# schematic.net
KiCad netlist of a schematic drawn in EAGLE
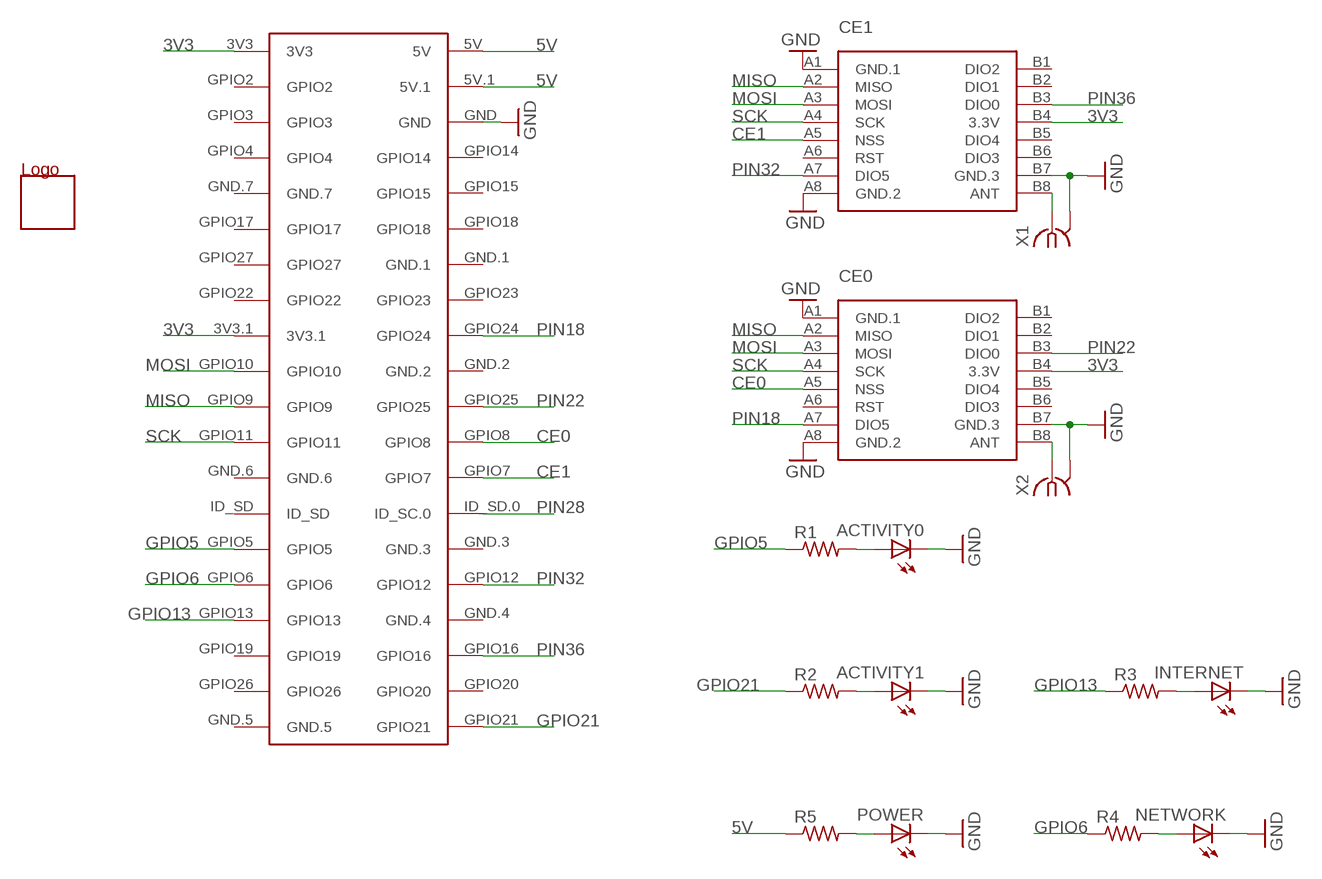
[diagram p0: schematic, sheet 1]

(export (version "E")
  (design (tool "Eeschema 10.0.6"))
  (components
    (comp (ref "ACTIVITY0")
      (value "LEDCHIPLED_0805")
      (footprint "eagle-import:CHIPLED_0805")
      (libsource (lib "eagle-import") (part "LEDCHIPLED_0805"))
    )
    (comp (ref "ACTIVITY1")
      (value "LEDCHIPLED_0805")
      (footprint "eagle-import:CHIPLED_0805")
      (libsource (lib "eagle-import") (part "LEDCHIPLED_0805"))
    )
    (comp (ref "CE0")
      (value "WIRELESS-LORA-RFM95W#SMD")
      (footprint "eagle-import:WIRELESS-LORA-RFM95W#SMD")
      (libsource (lib "eagle-import") (part "WIRELESS-LORA-RFM95W#SMD"))
    )
    (comp (ref "CE1")
      (value "WIRELESS-LORA-RFM95W#SMD")
      (footprint "eagle-import:WIRELESS-LORA-RFM95W#SMD")
      (libsource (lib "eagle-import") (part "WIRELESS-LORA-RFM95W#SMD"))
    )
    (comp (ref "INTERNET")
      (value "LEDCHIPLED_0805")
      (footprint "eagle-import:CHIPLED_0805")
      (libsource (lib "eagle-import") (part "LEDCHIPLED_0805"))
    )
    (comp (ref "NETWORK")
      (value "LEDCHIPLED_0805")
      (footprint "eagle-import:CHIPLED_0805")
      (libsource (lib "eagle-import") (part "LEDCHIPLED_0805"))
    )
    (comp (ref "POWER")
      (value "LEDCHIPLED_0805")
      (footprint "eagle-import:CHIPLED_0805")
      (libsource (lib "eagle-import") (part "LEDCHIPLED_0805"))
    )
    (comp (ref "R1")
      (value "R-US_R0805")
      (footprint "eagle-import:R0805")
      (libsource (lib "eagle-import") (part "R-US_R0805"))
    )
    (comp (ref "R2")
      (value "R-US_R0805")
      (footprint "eagle-import:R0805")
      (libsource (lib "eagle-import") (part "R-US_R0805"))
    )
    (comp (ref "R3")
      (value "R-US_R0805")
      (footprint "eagle-import:R0805")
      (libsource (lib "eagle-import") (part "R-US_R0805"))
    )
    (comp (ref "R4")
      (value "R-US_R0805")
      (footprint "eagle-import:R0805")
      (libsource (lib "eagle-import") (part "R-US_R0805"))
    )
    (comp (ref "R5")
      (value "R-US_R0805")
      (footprint "eagle-import:R0805")
      (libsource (lib "eagle-import") (part "R-US_R0805"))
    )
    (comp (ref "U$1")
      (value "PIZERO")
      (footprint "eagle-import:PIZERO")
      (libsource (lib "eagle-import") (part "PIZERO"))
    )
    (comp (ref "U$2")
      (value "REGANLOGO")
      (footprint "eagle-import:REGANLOGO")
      (libsource (lib "eagle-import") (part "REGANLOGO"))
    )
    (comp (ref "X1")
      (value "BU-SMA-V")
      (footprint "eagle-import:BU-SMA-V")
      (libsource (lib "eagle-import") (part "BU-SMA-V"))
    )
    (comp (ref "X2")
      (value "BU-SMA-V")
      (footprint "eagle-import:BU-SMA-V")
      (libsource (lib "eagle-import") (part "BU-SMA-V"))
    )
  )
  (nets
    (net (code "1") (name "/3V3") (class "Default")
      (node (ref "CE0") (pin "B4") (pinfunction "3.3V_B4") (pintype "power_in"))
      (node (ref "CE1") (pin "B4") (pinfunction "3.3V_B4") (pintype "power_in"))
      (node (ref "U$1") (pin "3V3") (pinfunction "3V3_3V3") (pintype "bidirectional"))
      (node (ref "U$1") (pin "3V3.1") (pinfunction "3V3.1_3V3.1") (pintype "bidirectional"))
    )
    (net (code "2") (name "/5V") (class "Default")
      (node (ref "R5") (pin "1") (pinfunction "1_1") (pintype "passive"))
      (node (ref "U$1") (pin "5V") (pinfunction "5V_5V") (pintype "bidirectional"))
      (node (ref "U$1") (pin "5V.1") (pinfunction "5V.1_5V.1") (pintype "bidirectional"))
    )
    (net (code "3") (name "/CE0") (class "Default")
      (node (ref "CE0") (pin "A5") (pinfunction "NSS_A5") (pintype "bidirectional"))
      (node (ref "U$1") (pin "GPIO8") (pinfunction "GPIO8_GPIO8") (pintype "bidirectional"))
    )
    (net (code "4") (name "/CE1") (class "Default")
      (node (ref "CE1") (pin "A5") (pinfunction "NSS_A5") (pintype "bidirectional"))
      (node (ref "U$1") (pin "GPIO7") (pinfunction "GPIO7_GPIO7") (pintype "bidirectional"))
    )
    (net (code "5") (name "/GPIO5") (class "Default")
      (node (ref "R1") (pin "1") (pinfunction "1_1") (pintype "passive"))
      (node (ref "U$1") (pin "GPIO5") (pinfunction "GPIO5_GPIO5") (pintype "bidirectional"))
    )
    (net (code "6") (name "/GPIO6") (class "Default")
      (node (ref "R4") (pin "1") (pinfunction "1_1") (pintype "passive"))
      (node (ref "U$1") (pin "GPIO6") (pinfunction "GPIO6_GPIO6") (pintype "bidirectional"))
    )
    (net (code "7") (name "/GPIO13") (class "Default")
      (node (ref "R3") (pin "1") (pinfunction "1_1") (pintype "passive"))
      (node (ref "U$1") (pin "GPIO13") (pinfunction "GPIO13_GPIO13") (pintype "bidirectional"))
    )
    (net (code "8") (name "/GPIO21") (class "Default")
      (node (ref "R2") (pin "1") (pinfunction "1_1") (pintype "passive"))
      (node (ref "U$1") (pin "GPIO21") (pinfunction "GPIO21_GPIO21") (pintype "bidirectional"))
    )
    (net (code "9") (name "/MISO") (class "Default")
      (node (ref "CE0") (pin "A2") (pinfunction "MISO_A2") (pintype "bidirectional"))
      (node (ref "CE1") (pin "A2") (pinfunction "MISO_A2") (pintype "bidirectional"))
      (node (ref "U$1") (pin "GPIO9") (pinfunction "GPIO9_GPIO9") (pintype "bidirectional"))
    )
    (net (code "10") (name "/MOSI") (class "Default")
      (node (ref "CE0") (pin "A3") (pinfunction "MOSI_A3") (pintype "bidirectional"))
      (node (ref "CE1") (pin "A3") (pinfunction "MOSI_A3") (pintype "bidirectional"))
      (node (ref "U$1") (pin "GPIO10") (pinfunction "GPIO10_GPIO10") (pintype "bidirectional"))
    )
    (net (code "11") (name "/PIN18") (class "Default")
      (node (ref "CE0") (pin "A7") (pinfunction "DIO5_A7") (pintype "bidirectional"))
      (node (ref "U$1") (pin "GPIO24") (pinfunction "GPIO24_GPIO24") (pintype "bidirectional"))
    )
    (net (code "12") (name "/PIN22") (class "Default")
      (node (ref "CE0") (pin "B3") (pinfunction "DIO0_B3") (pintype "bidirectional"))
      (node (ref "U$1") (pin "GPIO25") (pinfunction "GPIO25_GPIO25") (pintype "bidirectional"))
    )
    (net (code "13") (name "/PIN28") (class "Default")
      (node (ref "U$1") (pin "ID_SD.0") (pinfunction "ID_SC.0_ID_SD.0") (pintype "bidirectional"))
    )
    (net (code "14") (name "/PIN32") (class "Default")
      (node (ref "CE1") (pin "A7") (pinfunction "DIO5_A7") (pintype "bidirectional"))
      (node (ref "U$1") (pin "GPIO12") (pinfunction "GPIO12_GPIO12") (pintype "bidirectional"))
    )
    (net (code "15") (name "/PIN36") (class "Default")
      (node (ref "CE1") (pin "B3") (pinfunction "DIO0_B3") (pintype "bidirectional"))
      (node (ref "U$1") (pin "GPIO16") (pinfunction "GPIO16_GPIO16") (pintype "bidirectional"))
    )
    (net (code "16") (name "/SCK") (class "Default")
      (node (ref "CE0") (pin "A4") (pinfunction "SCK_A4") (pintype "bidirectional"))
      (node (ref "CE1") (pin "A4") (pinfunction "SCK_A4") (pintype "bidirectional"))
      (node (ref "U$1") (pin "GPIO11") (pinfunction "GPIO11_GPIO11") (pintype "bidirectional"))
    )
    (net (code "17") (name "GND") (class "Default")
      (node (ref "ACTIVITY0") (pin "C") (pinfunction "C_C") (pintype "passive"))
      (node (ref "ACTIVITY1") (pin "C") (pinfunction "C_C") (pintype "passive"))
      (node (ref "CE0") (pin "A1") (pinfunction "GND.1_A1") (pintype "power_in"))
      (node (ref "CE0") (pin "A8") (pinfunction "GND.2_A8") (pintype "power_in"))
      (node (ref "CE0") (pin "B7") (pinfunction "GND.3_B7") (pintype "power_in"))
      (node (ref "CE1") (pin "A1") (pinfunction "GND.1_A1") (pintype "power_in"))
      (node (ref "CE1") (pin "A8") (pinfunction "GND.2_A8") (pintype "power_in"))
      (node (ref "CE1") (pin "B7") (pinfunction "GND.3_B7") (pintype "power_in"))
      (node (ref "INTERNET") (pin "C") (pinfunction "C_C") (pintype "passive"))
      (node (ref "NETWORK") (pin "C") (pinfunction "C_C") (pintype "passive"))
      (node (ref "POWER") (pin "C") (pinfunction "C_C") (pintype "passive"))
      (node (ref "U$1") (pin "GND") (pinfunction "GND_GND") (pintype "bidirectional"))
      (node (ref "X1") (pin "2") (pinfunction "2_2") (pintype "passive"))
      (node (ref "X1") (pin "3") (pinfunction "2_3") (pintype "passive"))
      (node (ref "X1") (pin "4") (pinfunction "2_4") (pintype "passive"))
      (node (ref "X1") (pin "5") (pinfunction "2_5") (pintype "passive"))
      (node (ref "X2") (pin "2") (pinfunction "2_2") (pintype "passive"))
      (node (ref "X2") (pin "3") (pinfunction "2_3") (pintype "passive"))
      (node (ref "X2") (pin "4") (pinfunction "2_4") (pintype "passive"))
      (node (ref "X2") (pin "5") (pinfunction "2_5") (pintype "passive"))
    )
    (net (code "18") (name "Net-(ACTIVITY0-PadA)") (class "Default")
      (node (ref "ACTIVITY0") (pin "A") (pinfunction "A_A") (pintype "passive"))
      (node (ref "R1") (pin "2") (pinfunction "2_2") (pintype "passive"))
    )
    (net (code "19") (name "Net-(ACTIVITY1-PadA)") (class "Default")
      (node (ref "ACTIVITY1") (pin "A") (pinfunction "A_A") (pintype "passive"))
      (node (ref "R2") (pin "2") (pinfunction "2_2") (pintype "passive"))
    )
    (net (code "20") (name "Net-(CE0-ANT)") (class "Default")
      (node (ref "CE0") (pin "B8") (pinfunction "ANT_B8") (pintype "passive"))
      (node (ref "X2") (pin "1") (pinfunction "1_1") (pintype "passive"))
    )
    (net (code "21") (name "Net-(CE1-ANT)") (class "Default")
      (node (ref "CE1") (pin "B8") (pinfunction "ANT_B8") (pintype "passive"))
      (node (ref "X1") (pin "1") (pinfunction "1_1") (pintype "passive"))
    )
    (net (code "22") (name "Net-(INTERNET-PadA)") (class "Default")
      (node (ref "INTERNET") (pin "A") (pinfunction "A_A") (pintype "passive"))
      (node (ref "R3") (pin "2") (pinfunction "2_2") (pintype "passive"))
    )
    (net (code "23") (name "Net-(NETWORK-PadA)") (class "Default")
      (node (ref "NETWORK") (pin "A") (pinfunction "A_A") (pintype "passive"))
      (node (ref "R4") (pin "2") (pinfunction "2_2") (pintype "passive"))
    )
    (net (code "24") (name "Net-(POWER-PadA)") (class "Default")
      (node (ref "POWER") (pin "A") (pinfunction "A_A") (pintype "passive"))
      (node (ref "R5") (pin "2") (pinfunction "2_2") (pintype "passive"))
    )
    (net (code "25") (name "unconnected-(CE0-DIO1-PadB2)") (class "Default")
      (node (ref "CE0") (pin "B2") (pinfunction "DIO1_B2") (pintype "bidirectional"))
    )
    (net (code "26") (name "unconnected-(CE0-DIO2-PadB1)") (class "Default")
      (node (ref "CE0") (pin "B1") (pinfunction "DIO2_B1") (pintype "bidirectional"))
    )
    (net (code "27") (name "unconnected-(CE0-DIO3-PadB6)") (class "Default")
      (node (ref "CE0") (pin "B6") (pinfunction "DIO3_B6") (pintype "bidirectional"))
    )
    (net (code "28") (name "unconnected-(CE0-DIO4-PadB5)") (class "Default")
      (node (ref "CE0") (pin "B5") (pinfunction "DIO4_B5") (pintype "bidirectional"))
    )
    (net (code "29") (name "unconnected-(CE0-RST-PadA6)") (class "Default")
      (node (ref "CE0") (pin "A6") (pinfunction "RST_A6") (pintype "bidirectional"))
    )
    (net (code "30") (name "unconnected-(CE1-DIO1-PadB2)") (class "Default")
      (node (ref "CE1") (pin "B2") (pinfunction "DIO1_B2") (pintype "bidirectional"))
    )
    (net (code "31") (name "unconnected-(CE1-DIO2-PadB1)") (class "Default")
      (node (ref "CE1") (pin "B1") (pinfunction "DIO2_B1") (pintype "bidirectional"))
    )
    (net (code "32") (name "unconnected-(CE1-DIO3-PadB6)") (class "Default")
      (node (ref "CE1") (pin "B6") (pinfunction "DIO3_B6") (pintype "bidirectional"))
    )
    (net (code "33") (name "unconnected-(CE1-DIO4-PadB5)") (class "Default")
      (node (ref "CE1") (pin "B5") (pinfunction "DIO4_B5") (pintype "bidirectional"))
    )
    (net (code "34") (name "unconnected-(CE1-RST-PadA6)") (class "Default")
      (node (ref "CE1") (pin "A6") (pinfunction "RST_A6") (pintype "bidirectional"))
    )
    (net (code "35") (name "unconnected-(U$1-PadGND.1)") (class "Default")
      (node (ref "U$1") (pin "GND.1") (pinfunction "GND.1_GND.1") (pintype "bidirectional"))
    )
    (net (code "36") (name "unconnected-(U$1-PadGND.2)") (class "Default")
      (node (ref "U$1") (pin "GND.2") (pinfunction "GND.2_GND.2") (pintype "bidirectional"))
    )
    (net (code "37") (name "unconnected-(U$1-PadGND.3)") (class "Default")
      (node (ref "U$1") (pin "GND.3") (pinfunction "GND.3_GND.3") (pintype "bidirectional"))
    )
    (net (code "38") (name "unconnected-(U$1-PadGND.4)") (class "Default")
      (node (ref "U$1") (pin "GND.4") (pinfunction "GND.4_GND.4") (pintype "bidirectional"))
    )
    (net (code "39") (name "unconnected-(U$1-PadGND.5)") (class "Default")
      (node (ref "U$1") (pin "GND.5") (pinfunction "GND.5_GND.5") (pintype "bidirectional"))
    )
    (net (code "40") (name "unconnected-(U$1-PadGND.6)") (class "Default")
      (node (ref "U$1") (pin "GND.6") (pinfunction "GND.6_GND.6") (pintype "bidirectional"))
    )
    (net (code "41") (name "unconnected-(U$1-PadGND.7)") (class "Default")
      (node (ref "U$1") (pin "GND.7") (pinfunction "GND.7_GND.7") (pintype "bidirectional"))
    )
    (net (code "42") (name "unconnected-(U$1-PadGPIO2)") (class "Default")
      (node (ref "U$1") (pin "GPIO2") (pinfunction "GPIO2_GPIO2") (pintype "bidirectional"))
    )
    (net (code "43") (name "unconnected-(U$1-PadGPIO3)") (class "Default")
      (node (ref "U$1") (pin "GPIO3") (pinfunction "GPIO3_GPIO3") (pintype "bidirectional"))
    )
    (net (code "44") (name "unconnected-(U$1-PadGPIO4)") (class "Default")
      (node (ref "U$1") (pin "GPIO4") (pinfunction "GPIO4_GPIO4") (pintype "bidirectional"))
    )
    (net (code "45") (name "unconnected-(U$1-PadGPIO14)") (class "Default")
      (node (ref "U$1") (pin "GPIO14") (pinfunction "GPIO14_GPIO14") (pintype "bidirectional"))
    )
    (net (code "46") (name "unconnected-(U$1-PadGPIO15)") (class "Default")
      (node (ref "U$1") (pin "GPIO15") (pinfunction "GPIO15_GPIO15") (pintype "bidirectional"))
    )
    (net (code "47") (name "unconnected-(U$1-PadGPIO17)") (class "Default")
      (node (ref "U$1") (pin "GPIO17") (pinfunction "GPIO17_GPIO17") (pintype "bidirectional"))
    )
    (net (code "48") (name "unconnected-(U$1-PadGPIO18)") (class "Default")
      (node (ref "U$1") (pin "GPIO18") (pinfunction "GPIO18_GPIO18") (pintype "bidirectional"))
    )
    (net (code "49") (name "unconnected-(U$1-PadGPIO19)") (class "Default")
      (node (ref "U$1") (pin "GPIO19") (pinfunction "GPIO19_GPIO19") (pintype "bidirectional"))
    )
    (net (code "50") (name "unconnected-(U$1-PadGPIO20)") (class "Default")
      (node (ref "U$1") (pin "GPIO20") (pinfunction "GPIO20_GPIO20") (pintype "bidirectional"))
    )
    (net (code "51") (name "unconnected-(U$1-PadGPIO22)") (class "Default")
      (node (ref "U$1") (pin "GPIO22") (pinfunction "GPIO22_GPIO22") (pintype "bidirectional"))
    )
    (net (code "52") (name "unconnected-(U$1-PadGPIO23)") (class "Default")
      (node (ref "U$1") (pin "GPIO23") (pinfunction "GPIO23_GPIO23") (pintype "bidirectional"))
    )
    (net (code "53") (name "unconnected-(U$1-PadGPIO26)") (class "Default")
      (node (ref "U$1") (pin "GPIO26") (pinfunction "GPIO26_GPIO26") (pintype "bidirectional"))
    )
    (net (code "54") (name "unconnected-(U$1-PadGPIO27)") (class "Default")
      (node (ref "U$1") (pin "GPIO27") (pinfunction "GPIO27_GPIO27") (pintype "bidirectional"))
    )
    (net (code "55") (name "unconnected-(U$1-PadID_SD)") (class "Default")
      (node (ref "U$1") (pin "ID_SD") (pinfunction "ID_SD_ID_SD") (pintype "bidirectional"))
    )
  )
)
